# OGX360I-4CH_-_Middle_Man_P1_-_P2.net
KiCad netlist of a schematic drawn in EAGLE
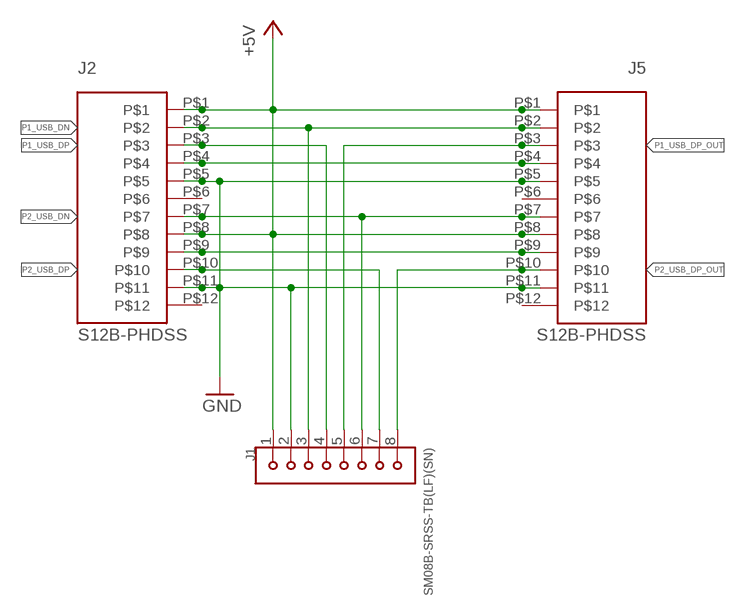
[diagram p0: schematic, sheet 1]

(export (version "E")
  (design (tool "Eeschema 10.0.6"))
  (components
    (comp (ref "J1")
      (value "SM08B-SRSS-TB(LF)(SN)")
      (footprint "eagle-import:JST_SM08B-SRSS-TB(LF)(SN)")
      (fields (field (name "MF") "JST Sales") (field (name "MP") "SM08B-SRSS-TB_LF__SN_"))
      (libsource (lib "eagle-import") (part "SM08B-SRSS-TB(LF)(SN)"))
    )
    (comp (ref "J2")
      (value "S12B-PHDSS")
      (footprint "eagle-import:S12B-PHDSS")
      (libsource (lib "eagle-import") (part "S12B-PHDSS"))
    )
    (comp (ref "J5")
      (value "S12B-PHDSS")
      (footprint "eagle-import:S12B-PHDSS")
      (libsource (lib "eagle-import") (part "S12B-PHDSS"))
    )
  )
  (nets
    (net (code "1") (name "+5V") (class "Default")
      (node (ref "J1") (pin "1") (pinfunction "1_1") (pintype "passive"))
      (node (ref "J2") (pin "P$1") (pinfunction "P$1_P$1") (pintype "bidirectional"))
      (node (ref "J2") (pin "P$8") (pinfunction "P$8_P$8") (pintype "bidirectional"))
      (node (ref "J5") (pin "P$1") (pinfunction "P$1_P$1") (pintype "bidirectional"))
      (node (ref "J5") (pin "P$8") (pinfunction "P$8_P$8") (pintype "bidirectional"))
    )
    (net (code "2") (name "GND") (class "Default")
      (node (ref "J1") (pin "2") (pinfunction "2_2") (pintype "passive"))
      (node (ref "J2") (pin "P$11") (pinfunction "P$11_P$11") (pintype "bidirectional"))
      (node (ref "J2") (pin "P$5") (pinfunction "P$5_P$5") (pintype "bidirectional"))
      (node (ref "J5") (pin "P$11") (pinfunction "P$11_P$11") (pintype "bidirectional"))
      (node (ref "J5") (pin "P$5") (pinfunction "P$5_P$5") (pintype "bidirectional"))
    )
    (net (code "3") (name "Net-(J2-PadP$4)") (class "Default")
      (node (ref "J2") (pin "P$4") (pinfunction "P$4_P$4") (pintype "bidirectional"))
      (node (ref "J5") (pin "P$4") (pinfunction "P$4_P$4") (pintype "bidirectional"))
    )
    (net (code "4") (name "Net-(J2-PadP$9)") (class "Default")
      (node (ref "J2") (pin "P$9") (pinfunction "P$9_P$9") (pintype "bidirectional"))
      (node (ref "J5") (pin "P$9") (pinfunction "P$9_P$9") (pintype "bidirectional"))
    )
    (net (code "5") (name "P1_USB_DN") (class "Default")
      (node (ref "J1") (pin "3") (pinfunction "3_3") (pintype "passive"))
      (node (ref "J2") (pin "P$2") (pinfunction "P$2_P$2") (pintype "bidirectional"))
      (node (ref "J5") (pin "P$2") (pinfunction "P$2_P$2") (pintype "bidirectional"))
    )
    (net (code "6") (name "P1_USB_DP") (class "Default")
      (node (ref "J1") (pin "4") (pinfunction "4_4") (pintype "passive"))
      (node (ref "J2") (pin "P$3") (pinfunction "P$3_P$3") (pintype "bidirectional"))
    )
    (net (code "7") (name "P1_USB_DP_OUT") (class "Default")
      (node (ref "J1") (pin "5") (pinfunction "5_5") (pintype "passive"))
      (node (ref "J5") (pin "P$3") (pinfunction "P$3_P$3") (pintype "bidirectional"))
    )
    (net (code "8") (name "P2_USB_DN") (class "Default")
      (node (ref "J1") (pin "6") (pinfunction "6_6") (pintype "passive"))
      (node (ref "J2") (pin "P$7") (pinfunction "P$7_P$7") (pintype "bidirectional"))
      (node (ref "J5") (pin "P$7") (pinfunction "P$7_P$7") (pintype "bidirectional"))
    )
    (net (code "9") (name "P2_USB_DP") (class "Default")
      (node (ref "J1") (pin "7") (pinfunction "7_7") (pintype "passive"))
      (node (ref "J2") (pin "P$10") (pinfunction "P$10_P$10") (pintype "bidirectional"))
    )
    (net (code "10") (name "P2_USB_DP_OUT") (class "Default")
      (node (ref "J1") (pin "8") (pinfunction "8_8") (pintype "passive"))
      (node (ref "J5") (pin "P$10") (pinfunction "P$10_P$10") (pintype "bidirectional"))
    )
    (net (code "11") (name "unconnected-(J2-PadP$6)") (class "Default")
      (node (ref "J2") (pin "P$6") (pinfunction "P$6_P$6") (pintype "bidirectional"))
    )
    (net (code "12") (name "unconnected-(J2-PadP$12)") (class "Default")
      (node (ref "J2") (pin "P$12") (pinfunction "P$12_P$12") (pintype "bidirectional"))
    )
    (net (code "13") (name "unconnected-(J5-PadP$6)") (class "Default")
      (node (ref "J5") (pin "P$6") (pinfunction "P$6_P$6") (pintype "bidirectional"))
    )
    (net (code "14") (name "unconnected-(J5-PadP$12)") (class "Default")
      (node (ref "J5") (pin "P$12") (pinfunction "P$12_P$12") (pintype "bidirectional"))
    )
  )
)
